# YOTSUBA_GNSS-receiver_MAX_ver_1_4_1.net
KiCad netlist of a schematic drawn in EAGLE
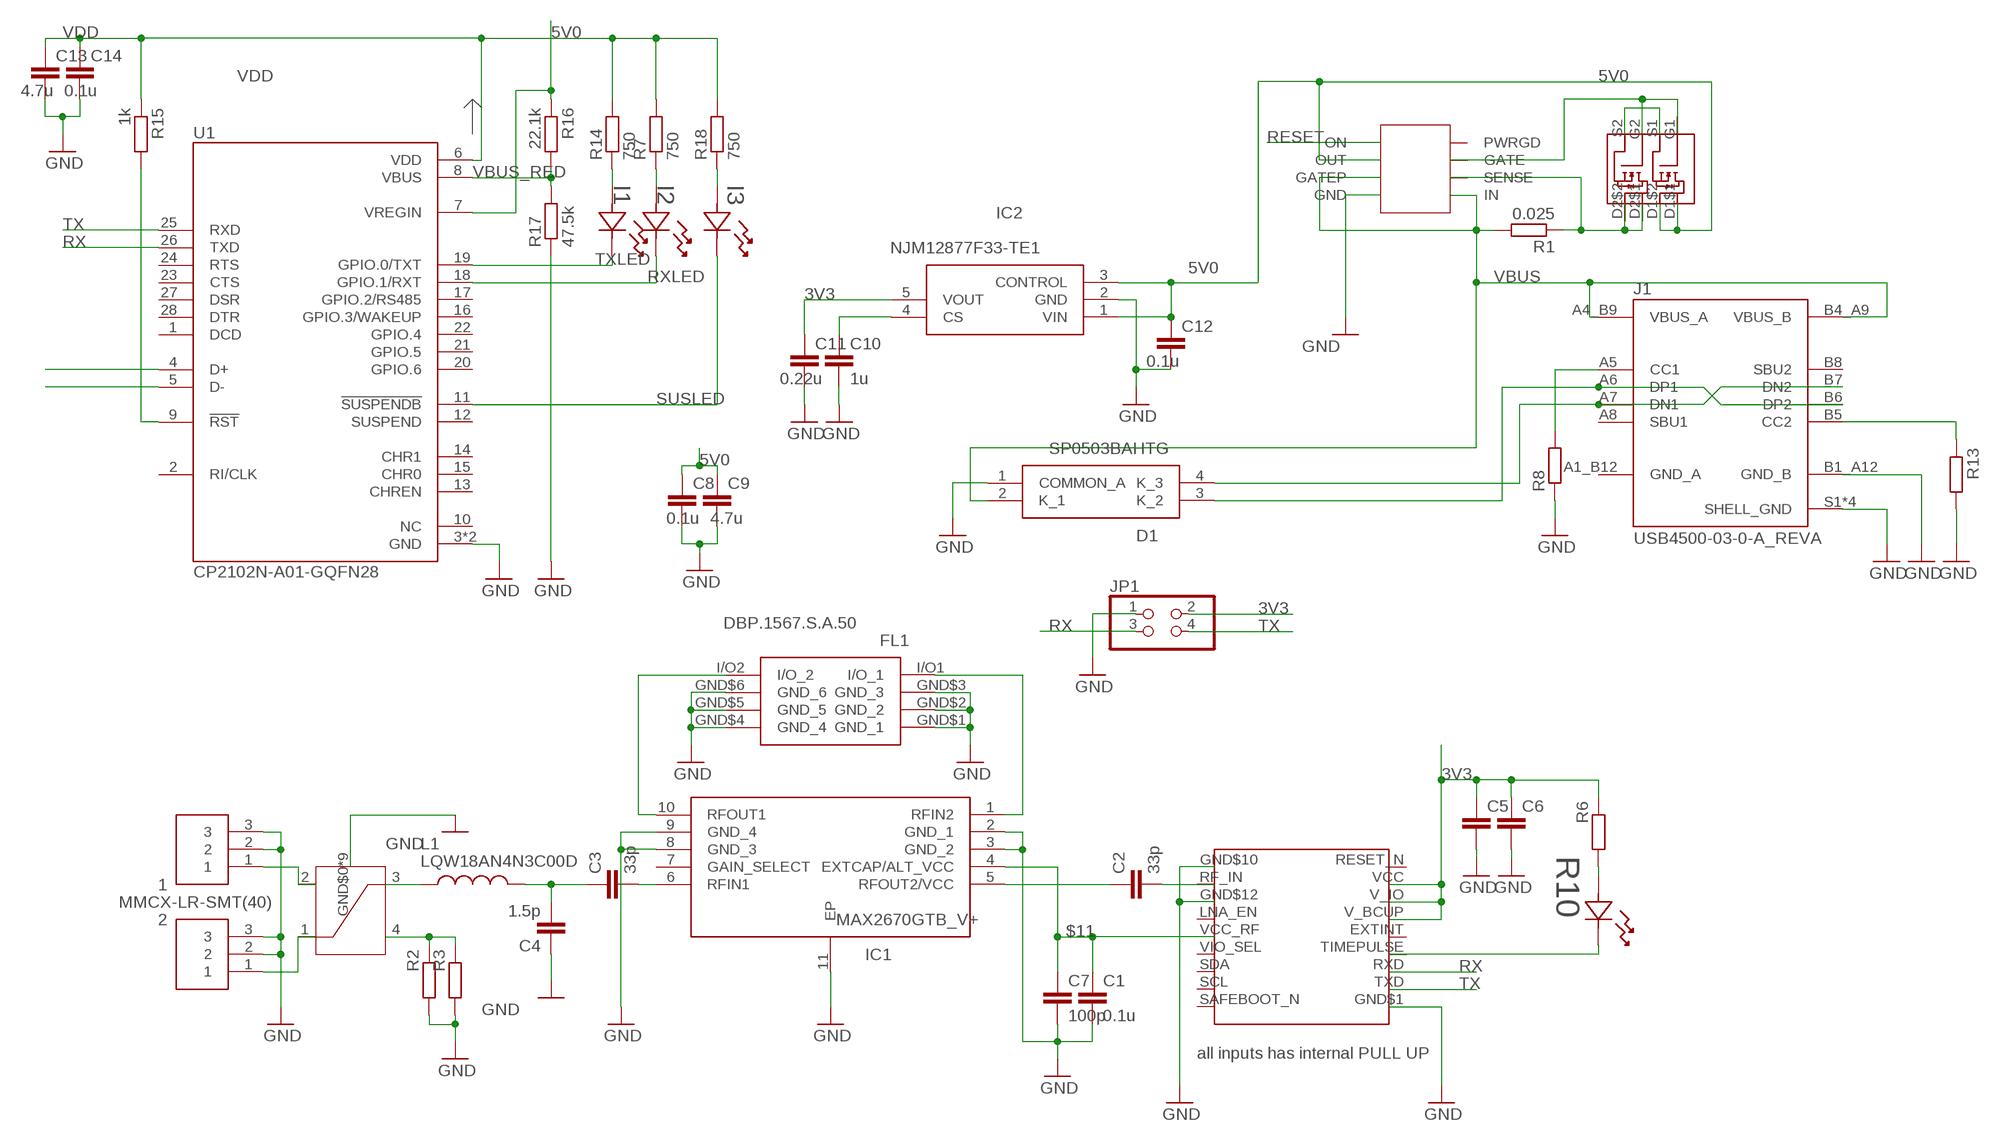
[diagram p0: schematic, sheet 1]

(export (version "E")
  (design (tool "Eeschema 10.0.6"))
  (components
    (comp (ref "1")
      (value "MMCX-LR-SMT(40)")
      (footprint "eagle-import:MMCX-LR-SMT(40)")
      (libsource (lib "eagle-import") (part "MMCX-LR-SMT(40)"))
    )
    (comp (ref "2")
      (value "MMCX-LR-SMT(40)")
      (footprint "eagle-import:MMCX-LR-SMT(40)")
      (libsource (lib "eagle-import") (part "MMCX-LR-SMT(40)"))
    )
    (comp (ref "C1")
      (value "0.1u")
      (footprint "eagle-import:C1608")
      (libsource (lib "eagle-import") (part "C-EUC1608"))
    )
    (comp (ref "C2")
      (value "33p")
      (footprint "eagle-import:C1608")
      (libsource (lib "eagle-import") (part "C-EUC1608"))
    )
    (comp (ref "C3")
      (value "33p")
      (footprint "eagle-import:C1608")
      (libsource (lib "eagle-import") (part "C-EUC1608"))
    )
    (comp (ref "C4")
      (value "1.5p")
      (footprint "eagle-import:C1608")
      (libsource (lib "eagle-import") (part "C-EUC1608"))
    )
    (comp (ref "C5")
      (value "C-EUC1608")
      (footprint "eagle-import:C1608")
      (libsource (lib "eagle-import") (part "C-EUC1608"))
    )
    (comp (ref "C6")
      (value "C-EUC1608")
      (footprint "eagle-import:C1608")
      (libsource (lib "eagle-import") (part "C-EUC1608"))
    )
    (comp (ref "C7")
      (value "100p")
      (footprint "eagle-import:C1608")
      (libsource (lib "eagle-import") (part "C-EUC1608"))
    )
    (comp (ref "C8")
      (value "0.1u")
      (footprint "eagle-import:C1608")
      (libsource (lib "eagle-import") (part "C-EUC1608"))
    )
    (comp (ref "C9")
      (value "4.7u")
      (footprint "eagle-import:C1608")
      (libsource (lib "eagle-import") (part "C-EUC1608"))
    )
    (comp (ref "C10")
      (value "1u")
      (footprint "eagle-import:C1608")
      (libsource (lib "eagle-import") (part "C-EUC1608"))
    )
    (comp (ref "C11")
      (value "0.22u")
      (footprint "eagle-import:C1608")
      (libsource (lib "eagle-import") (part "C-EUC1608"))
    )
    (comp (ref "C12")
      (value "0.1u")
      (footprint "eagle-import:C1608")
      (libsource (lib "eagle-import") (part "C-EUC1608"))
    )
    (comp (ref "C13")
      (value "4.7u")
      (footprint "eagle-import:C1608")
      (libsource (lib "eagle-import") (part "C-EUC1608"))
    )
    (comp (ref "C14")
      (value "0.1u")
      (footprint "eagle-import:C1608")
      (libsource (lib "eagle-import") (part "C-EUC1608"))
    )
    (comp (ref "D1")
      (value "SP0503BAHTG")
      (footprint "eagle-import:SP0503BAHTG")
      (fields (field (name "MOUSER_PART_NUMBER") "576-SP0503BAHTG"))
      (libsource (lib "eagle-import") (part "SP0503BAHTG"))
    )
    (comp (ref "FL1")
      (value "DBP.1567.S.A.50")
      (footprint "eagle-import:DBP1567SA50")
      (libsource (lib "eagle-import") (part "DBP.1567.S.A.50"))
    )
    (comp (ref "I1")
      (value "SML-E12P8WT86")
      (footprint "eagle-import:LED_SMLD12_ROM")
      (fields (field (name "COPYRIGHT") "Copyright (C) 2023 Ultra Librarian. All rights reserved."))
      (libsource (lib "eagle-import") (part "SML-E12P8WT86"))
    )
    (comp (ref "I2")
      (value "SML-E12P8WT86")
      (footprint "eagle-import:LED_SMLD12_ROM")
      (fields (field (name "COPYRIGHT") "Copyright (C) 2023 Ultra Librarian. All rights reserved."))
      (libsource (lib "eagle-import") (part "SML-E12P8WT86"))
    )
    (comp (ref "I3")
      (value "SML-E12P8WT86")
      (footprint "eagle-import:LED_SMLD12_ROM")
      (fields (field (name "COPYRIGHT") "Copyright (C) 2023 Ultra Librarian. All rights reserved."))
      (libsource (lib "eagle-import") (part "SML-E12P8WT86"))
    )
    (comp (ref "IC1")
      (value "MAX2670GTB_V+")
      (footprint "eagle-import:SON50P300X300X80-11N")
      (fields
        (field (name "MANUFACTURER_PART_NUMBER") "MAX2670GTB/V+")
        (field (name "MOUSER_PART_NUMBER") "700-MAX2670GTB/V+")
      )
      (libsource (lib "eagle-import") (part "MAX2670GTB_V+"))
    )
    (comp (ref "IC2")
      (value "NJM12877F33-TE1")
      (footprint "eagle-import:SOT95P280X120-5N")
      (fields (field (name "MOUSER_PART_NUMBER") "513-NJM12877F33-TE1"))
      (libsource (lib "eagle-import") (part "NJM12877F33-TE1"))
    )
    (comp (ref "J1")
      (value "USB4500-03-0-A_REVA")
      (footprint "eagle-import:GCT_USB4500-03-0-A_REVA")
      (fields
        (field (name "DIGI-KEY_PART_NUMBER") "2073-USB4500-03-0-ATR-ND")
        (field (name "MF") "Global Connector Technology")
        (field (name "MP") "USB4500-03-0-A")
      )
      (libsource (lib "eagle-import") (part "USB4500-03-0-A_REVA"))
    )
    (comp (ref "JP1")
      (value "PINHD-2X2")
      (footprint "eagle-import:2X02")
      (libsource (lib "eagle-import") (part "PINHD-2X2"))
    )
    (comp (ref "L1")
      (value "LQW18AN4N3C00D")
      (footprint "eagle-import:INDC1608X100N")
      (fields (field (name "DIGIKEY_PART_NUMBER") "490-6896-2-ND") (field (name "MF") "Murata"))
      (libsource (lib "eagle-import") (part "LQW18AN4N3C00D"))
    )
    (comp (ref "R1")
      (value "0.025")
      (footprint "eagle-import:R0603")
      (libsource (lib "eagle-import") (part "R-EU_R0603"))
    )
    (comp (ref "R2")
      (value "R-EU_R0603")
      (footprint "eagle-import:R0603")
      (libsource (lib "eagle-import") (part "R-EU_R0603"))
    )
    (comp (ref "R3")
      (value "R-EU_R0603")
      (footprint "eagle-import:R0603")
      (libsource (lib "eagle-import") (part "R-EU_R0603"))
    )
    (comp (ref "R6")
      (value "R-EU_R0603")
      (footprint "eagle-import:R0603")
      (libsource (lib "eagle-import") (part "R-EU_R0603"))
    )
    (comp (ref "R7")
      (value "750")
      (footprint "eagle-import:R0603")
      (libsource (lib "eagle-import") (part "R-EU_R0603"))
    )
    (comp (ref "R8")
      (value "R-EU_R0603")
      (footprint "eagle-import:R0603")
      (libsource (lib "eagle-import") (part "R-EU_R0603"))
    )
    (comp (ref "R10")
      (value "SML-E12P8WT86")
      (footprint "eagle-import:LED_SMLD12_ROM")
      (fields (field (name "COPYRIGHT") "Copyright (C) 2023 Ultra Librarian. All rights reserved."))
      (libsource (lib "eagle-import") (part "SML-E12P8WT86"))
    )
    (comp (ref "R13")
      (value "R-EU_R0603")
      (footprint "eagle-import:R0603")
      (libsource (lib "eagle-import") (part "R-EU_R0603"))
    )
    (comp (ref "R14")
      (value "750")
      (footprint "eagle-import:R0603")
      (libsource (lib "eagle-import") (part "R-EU_R0603"))
    )
    (comp (ref "R15")
      (value "1k")
      (footprint "eagle-import:R0603")
      (libsource (lib "eagle-import") (part "R-EU_R0603"))
    )
    (comp (ref "R16")
      (value "22.1k")
      (footprint "eagle-import:R0603")
      (libsource (lib "eagle-import") (part "R-EU_R0603"))
    )
    (comp (ref "R17")
      (value "47.5k")
      (footprint "eagle-import:R0603")
      (libsource (lib "eagle-import") (part "R-EU_R0603"))
    )
    (comp (ref "R18")
      (value "750")
      (footprint "eagle-import:R0603")
      (libsource (lib "eagle-import") (part "R-EU_R0603"))
    )
    (comp (ref "U$1")
      (value "MAX_M10S")
      (footprint "eagle-import:MAX-M10S")
      (libsource (lib "eagle-import") (part "MAX_M10S"))
    )
    (comp (ref "U$3")
      (value "HC125.A")
      (footprint "eagle-import:HC125.A")
      (libsource (lib "eagle-import") (part "HC125.A"))
    )
    (comp (ref "U$7")
      (value "DMG6898LSD")
      (footprint "eagle-import:SOIC127P600X150-8N")
      (libsource (lib "eagle-import") (part "DMG6898LSD"))
    )
    (comp (ref "U$8")
      (value "LTC4361")
      (footprint "eagle-import:SOP65P280X100-8N")
      (libsource (lib "eagle-import") (part "LTC4361"))
    )
    (comp (ref "U1")
      (value "CP2102N-A01-GQFN28")
      (footprint "eagle-import:QFN50P500X500X80-29N")
      (fields (field (name "MF") "Silicon Labs"))
      (libsource (lib "eagle-import") (part "CP2102N-A01-GQFN28"))
    )
  )
  (nets
    (net (code "1") (name "/$11") (class "Default")
      (node (ref "C1") (pin "1") (pinfunction "1_1") (pintype "passive"))
      (node (ref "C7") (pin "1") (pinfunction "1_1") (pintype "passive"))
      (node (ref "IC1") (pin "4") (pinfunction "EXTCAP/ALT_VCC_4") (pintype "bidirectional"))
      (node (ref "U$1") (pin "VCC_RF") (pinfunction "VCC_RF_VCC_RF") (pintype "bidirectional"))
    )
    (net (code "2") (name "/3V3") (class "Default")
      (node (ref "C11") (pin "1") (pinfunction "1_1") (pintype "passive"))
      (node (ref "C5") (pin "1") (pinfunction "1_1") (pintype "passive"))
      (node (ref "C6") (pin "1") (pinfunction "1_1") (pintype "passive"))
      (node (ref "IC2") (pin "5") (pinfunction "VOUT_5") (pintype "bidirectional"))
      (node (ref "JP1") (pin "2") (pinfunction "2_2") (pintype "passive"))
      (node (ref "R6") (pin "2") (pinfunction "2_2") (pintype "passive"))
      (node (ref "U$1") (pin "VCC") (pinfunction "VCC_VCC") (pintype "bidirectional"))
      (node (ref "U$1") (pin "V_BCUP") (pinfunction "V_BCKP_V_BCUP") (pintype "bidirectional"))
      (node (ref "U$1") (pin "V_IO") (pinfunction "V_IO_V_IO") (pintype "bidirectional"))
    )
    (net (code "3") (name "/5V0") (class "Default")
      (node (ref "C12") (pin "1") (pinfunction "1_1") (pintype "passive"))
      (node (ref "C8") (pin "1") (pinfunction "1_1") (pintype "passive"))
      (node (ref "C9") (pin "1") (pinfunction "1_1") (pintype "passive"))
      (node (ref "IC2") (pin "1") (pinfunction "VIN_1") (pintype "bidirectional"))
      (node (ref "IC2") (pin "3") (pinfunction "CONTROL_3") (pintype "bidirectional"))
      (node (ref "R16") (pin "1") (pinfunction "1_1") (pintype "passive"))
      (node (ref "U$7") (pin "D1$1") (pinfunction "D1$1_D1$1") (pintype "bidirectional"))
      (node (ref "U$7") (pin "D1$2") (pinfunction "D1$2_D1$2") (pintype "bidirectional"))
      (node (ref "U$8") (pin "OUT") (pinfunction "OUT_OUT") (pintype "bidirectional"))
      (node (ref "U1") (pin "7") (pinfunction "VREGIN_7") (pintype "power_in"))
    )
    (net (code "4") (name "/D+") (class "Default")
      (node (ref "D1") (pin "3") (pinfunction "K_2_3") (pintype "bidirectional"))
      (node (ref "J1") (pin "A6") (pinfunction "DP1_A6") (pintype "bidirectional"))
      (node (ref "J1") (pin "B6") (pinfunction "DP2_B6") (pintype "bidirectional"))
      (node (ref "U1") (pin "4") (pinfunction "D+_4") (pintype "bidirectional"))
    )
    (net (code "5") (name "/D-") (class "Default")
      (node (ref "D1") (pin "4") (pinfunction "K_3_4") (pintype "bidirectional"))
      (node (ref "J1") (pin "A7") (pinfunction "DN1_A7") (pintype "bidirectional"))
      (node (ref "J1") (pin "B7") (pinfunction "DN2_B7") (pintype "bidirectional"))
      (node (ref "U1") (pin "5") (pinfunction "D-_5") (pintype "bidirectional"))
    )
    (net (code "6") (name "/GND_A") (class "Default")
      (node (ref "J1") (pin "A1_B12") (pinfunction "GND_A_A1_B12") (pintype "power_in"))
    )
    (net (code "7") (name "/RESET") (class "Default")
      (node (ref "U$8") (pin "ON") (pinfunction "ON_ON") (pintype "bidirectional"))
    )
    (net (code "8") (name "/RX") (class "Default")
      (node (ref "JP1") (pin "3") (pinfunction "3_3") (pintype "passive"))
      (node (ref "U$1") (pin "RXD") (pinfunction "RXD_RXD") (pintype "bidirectional"))
      (node (ref "U1") (pin "26") (pinfunction "TXD_26") (pintype "output"))
    )
    (net (code "9") (name "/RXLED") (class "Default")
      (node (ref "I2") (pin "1") (pinfunction "1_1") (pintype "passive"))
      (node (ref "U1") (pin "18") (pinfunction "GPIO.1/RXT_18") (pintype "bidirectional"))
    )
    (net (code "10") (name "/SUSLED") (class "Default")
      (node (ref "I3") (pin "1") (pinfunction "1_1") (pintype "passive"))
      (node (ref "U1") (pin "11") (pinfunction "~{SUSPENDB}_11") (pintype "output"))
    )
    (net (code "11") (name "/TX") (class "Default")
      (node (ref "JP1") (pin "4") (pinfunction "4_4") (pintype "passive"))
      (node (ref "U$1") (pin "TXD") (pinfunction "TXD_TXD") (pintype "bidirectional"))
      (node (ref "U1") (pin "25") (pinfunction "RXD_25") (pintype "input"))
    )
    (net (code "12") (name "/TXLED") (class "Default")
      (node (ref "I1") (pin "1") (pinfunction "1_1") (pintype "passive"))
      (node (ref "U1") (pin "19") (pinfunction "GPIO.0/TXT_19") (pintype "bidirectional"))
    )
    (net (code "13") (name "/VBUS") (class "Default")
      (node (ref "D1") (pin "2") (pinfunction "K_1_2") (pintype "bidirectional"))
      (node (ref "J1") (pin "A4_B9") (pinfunction "VBUS_A_A4_B9") (pintype "power_in"))
      (node (ref "J1") (pin "B4_A9") (pinfunction "VBUS_B_B4_A9") (pintype "power_in"))
      (node (ref "R1") (pin "2") (pinfunction "2_2") (pintype "passive"))
      (node (ref "U$8") (pin "GATEP") (pinfunction "GATEP_GATEP") (pintype "bidirectional"))
      (node (ref "U$8") (pin "IN") (pinfunction "IN_IN") (pintype "bidirectional"))
    )
    (net (code "14") (name "/VBUS_RED") (class "Default")
      (node (ref "R16") (pin "2") (pinfunction "2_2") (pintype "passive"))
      (node (ref "R17") (pin "2") (pinfunction "2_2") (pintype "passive"))
      (node (ref "U1") (pin "8") (pinfunction "VBUS_8") (pintype "power_in"))
    )
    (net (code "15") (name "/VDD") (class "Default")
      (node (ref "C13") (pin "1") (pinfunction "1_1") (pintype "passive"))
      (node (ref "C14") (pin "1") (pinfunction "1_1") (pintype "passive"))
      (node (ref "R14") (pin "2") (pinfunction "2_2") (pintype "passive"))
      (node (ref "R15") (pin "1") (pinfunction "1_1") (pintype "passive"))
      (node (ref "R18") (pin "2") (pinfunction "2_2") (pintype "passive"))
      (node (ref "R7") (pin "2") (pinfunction "2_2") (pintype "passive"))
      (node (ref "U1") (pin "6") (pinfunction "VDD_6") (pintype "power_in"))
    )
    (net (code "16") (name "GND") (class "Default")
      (node (ref "1") (pin "2") (pinfunction "2_2") (pintype "bidirectional"))
      (node (ref "1") (pin "3") (pinfunction "3_3") (pintype "bidirectional"))
      (node (ref "2") (pin "2") (pinfunction "2_2") (pintype "bidirectional"))
      (node (ref "2") (pin "3") (pinfunction "3_3") (pintype "bidirectional"))
      (node (ref "C1") (pin "2") (pinfunction "2_2") (pintype "passive"))
      (node (ref "C10") (pin "2") (pinfunction "2_2") (pintype "passive"))
      (node (ref "C11") (pin "2") (pinfunction "2_2") (pintype "passive"))
      (node (ref "C12") (pin "2") (pinfunction "2_2") (pintype "passive"))
      (node (ref "C13") (pin "2") (pinfunction "2_2") (pintype "passive"))
      (node (ref "C14") (pin "2") (pinfunction "2_2") (pintype "passive"))
      (node (ref "C4") (pin "1") (pinfunction "1_1") (pintype "passive"))
      (node (ref "C5") (pin "2") (pinfunction "2_2") (pintype "passive"))
      (node (ref "C6") (pin "2") (pinfunction "2_2") (pintype "passive"))
      (node (ref "C7") (pin "2") (pinfunction "2_2") (pintype "passive"))
      (node (ref "C8") (pin "2") (pinfunction "2_2") (pintype "passive"))
      (node (ref "C9") (pin "2") (pinfunction "2_2") (pintype "passive"))
      (node (ref "D1") (pin "1") (pinfunction "COMMON_A_1") (pintype "bidirectional"))
      (node (ref "FL1") (pin "GND$1") (pinfunction "GND_1_GND$1") (pintype "bidirectional"))
      (node (ref "FL1") (pin "GND$2") (pinfunction "GND_2_GND$2") (pintype "bidirectional"))
      (node (ref "FL1") (pin "GND$3") (pinfunction "GND_3_GND$3") (pintype "bidirectional"))
      (node (ref "FL1") (pin "GND$4") (pinfunction "GND_4_GND$4") (pintype "bidirectional"))
      (node (ref "FL1") (pin "GND$5") (pinfunction "GND_5_GND$5") (pintype "bidirectional"))
      (node (ref "FL1") (pin "GND$6") (pinfunction "GND_6_GND$6") (pintype "bidirectional"))
      (node (ref "IC1") (pin "11") (pinfunction "EP_11") (pintype "bidirectional"))
      (node (ref "IC1") (pin "2") (pinfunction "GND_1_2") (pintype "bidirectional"))
      (node (ref "IC1") (pin "3") (pinfunction "GND_2_3") (pintype "bidirectional"))
      (node (ref "IC1") (pin "8") (pinfunction "GND_3_8") (pintype "bidirectional"))
      (node (ref "IC1") (pin "9") (pinfunction "GND_4_9") (pintype "bidirectional"))
      (node (ref "IC2") (pin "2") (pinfunction "GND_2") (pintype "bidirectional"))
      (node (ref "J1") (pin "B1_A12") (pinfunction "GND_B_B1_A12") (pintype "power_in"))
      (node (ref "J1") (pin "S1") (pinfunction "SHELL_GND_S1") (pintype "power_in"))
      (node (ref "J1") (pin "S2") (pinfunction "SHELL_GND_S2") (pintype "power_in"))
      (node (ref "J1") (pin "S3") (pinfunction "SHELL_GND_S3") (pintype "power_in"))
      (node (ref "J1") (pin "S4") (pinfunction "SHELL_GND_S4") (pintype "power_in"))
      (node (ref "JP1") (pin "1") (pinfunction "1_1") (pintype "passive"))
      (node (ref "R13") (pin "2") (pinfunction "2_2") (pintype "passive"))
      (node (ref "R17") (pin "1") (pinfunction "1_1") (pintype "passive"))
      (node (ref "R2") (pin "1") (pinfunction "1_1") (pintype "passive"))
      (node (ref "R3") (pin "1") (pinfunction "1_1") (pintype "passive"))
      (node (ref "R8") (pin "1") (pinfunction "1_1") (pintype "passive"))
      (node (ref "U$1") (pin "GND$1") (pinfunction "GND$1_GND$1") (pintype "bidirectional"))
      (node (ref "U$1") (pin "GND$10") (pinfunction "GND$10_GND$10") (pintype "bidirectional"))
      (node (ref "U$1") (pin "GND$12") (pinfunction "GND$12_GND$12") (pintype "bidirectional"))
      (node (ref "U$3") (pin "GND$0") (pinfunction "GND_GND$0") (pintype "bidirectional"))
      (node (ref "U$3") (pin "GND$1") (pinfunction "GND_GND$1") (pintype "bidirectional"))
      (node (ref "U$3") (pin "GND$2") (pinfunction "GND_GND$2") (pintype "bidirectional"))
      (node (ref "U$3") (pin "GND$3") (pinfunction "GND_GND$3") (pintype "bidirectional"))
      (node (ref "U$3") (pin "GND$4") (pinfunction "GND_GND$4") (pintype "bidirectional"))
      (node (ref "U$3") (pin "GND$5") (pinfunction "GND_GND$5") (pintype "bidirectional"))
      (node (ref "U$3") (pin "GND$6") (pinfunction "GND_GND$6") (pintype "bidirectional"))
      (node (ref "U$3") (pin "GND$7") (pinfunction "GND_GND$7") (pintype "bidirectional"))
      (node (ref "U$3") (pin "GND$8") (pinfunction "GND_GND$8") (pintype "bidirectional"))
      (node (ref "U$8") (pin "GND") (pinfunction "GND_GND") (pintype "bidirectional"))
      (node (ref "U1") (pin "29") (pinfunction "GND_29") (pintype "power_in"))
      (node (ref "U1") (pin "3") (pinfunction "GND_3") (pintype "power_in"))
    )
    (net (code "17") (name "Net-(1-Pad1)") (class "Default")
      (node (ref "1") (pin "1") (pinfunction "1_1") (pintype "bidirectional"))
      (node (ref "U$3") (pin "2") (pinfunction "2_2") (pintype "bidirectional"))
    )
    (net (code "18") (name "Net-(2-Pad1)") (class "Default")
      (node (ref "2") (pin "1") (pinfunction "1_1") (pintype "bidirectional"))
      (node (ref "U$3") (pin "1") (pinfunction "1_1") (pintype "bidirectional"))
    )
    (net (code "19") (name "Net-(C2-Pad2)") (class "Default")
      (node (ref "C2") (pin "2") (pinfunction "2_2") (pintype "passive"))
      (node (ref "U$1") (pin "RF_IN") (pinfunction "RF_IN_RF_IN") (pintype "bidirectional"))
    )
    (net (code "20") (name "Net-(C3-Pad1)") (class "Default")
      (node (ref "C3") (pin "1") (pinfunction "1_1") (pintype "passive"))
      (node (ref "C4") (pin "2") (pinfunction "2_2") (pintype "passive"))
      (node (ref "L1") (pin "2") (pinfunction "2_2") (pintype "passive"))
    )
    (net (code "21") (name "Net-(FL1-I{slash}O_1)") (class "Default")
      (node (ref "FL1") (pin "I/O1") (pinfunction "I/O_1_I/O1") (pintype "bidirectional"))
      (node (ref "IC1") (pin "1") (pinfunction "RFIN2_1") (pintype "bidirectional"))
    )
    (net (code "22") (name "Net-(FL1-I{slash}O_2)") (class "Default")
      (node (ref "FL1") (pin "I/O2") (pinfunction "I/O_2_I/O2") (pintype "bidirectional"))
      (node (ref "IC1") (pin "10") (pinfunction "RFOUT1_10") (pintype "bidirectional"))
    )
    (net (code "23") (name "Net-(I1-Pad2)") (class "Default")
      (node (ref "I1") (pin "2") (pinfunction "2_2") (pintype "passive"))
      (node (ref "R14") (pin "1") (pinfunction "1_1") (pintype "passive"))
    )
    (net (code "24") (name "Net-(I2-Pad2)") (class "Default")
      (node (ref "I2") (pin "2") (pinfunction "2_2") (pintype "passive"))
      (node (ref "R7") (pin "1") (pinfunction "1_1") (pintype "passive"))
    )
    (net (code "25") (name "Net-(I3-Pad2)") (class "Default")
      (node (ref "I3") (pin "2") (pinfunction "2_2") (pintype "passive"))
      (node (ref "R18") (pin "1") (pinfunction "1_1") (pintype "passive"))
    )
    (net (code "26") (name "Net-(IC1-RFIN1)") (class "Default")
      (node (ref "C3") (pin "2") (pinfunction "2_2") (pintype "passive"))
      (node (ref "IC1") (pin "6") (pinfunction "RFIN1_6") (pintype "bidirectional"))
    )
    (net (code "27") (name "Net-(IC1-RFOUT2{slash}VCC)") (class "Default")
      (node (ref "C2") (pin "1") (pinfunction "1_1") (pintype "passive"))
      (node (ref "IC1") (pin "5") (pinfunction "RFOUT2/VCC_5") (pintype "bidirectional"))
    )
    (net (code "28") (name "Net-(IC2-CS)") (class "Default")
      (node (ref "C10") (pin "1") (pinfunction "1_1") (pintype "passive"))
      (node (ref "IC2") (pin "4") (pinfunction "CS_4") (pintype "bidirectional"))
    )
    (net (code "29") (name "Net-(J1-CC1)") (class "Default")
      (node (ref "J1") (pin "A5") (pinfunction "CC1_A5") (pintype "bidirectional"))
      (node (ref "R8") (pin "2") (pinfunction "2_2") (pintype "passive"))
    )
    (net (code "30") (name "Net-(J1-CC2)") (class "Default")
      (node (ref "J1") (pin "B5") (pinfunction "CC2_B5") (pintype "bidirectional"))
      (node (ref "R13") (pin "1") (pinfunction "1_1") (pintype "passive"))
    )
    (net (code "31") (name "Net-(L1-Pad1)") (class "Default")
      (node (ref "L1") (pin "1") (pinfunction "1_1") (pintype "passive"))
      (node (ref "U$3") (pin "3") (pinfunction "3_3") (pintype "bidirectional"))
    )
    (net (code "32") (name "Net-(R1-Pad1)") (class "Default")
      (node (ref "R1") (pin "1") (pinfunction "1_1") (pintype "passive"))
      (node (ref "U$7") (pin "D2$1") (pinfunction "D2$1_D2$1") (pintype "bidirectional"))
      (node (ref "U$7") (pin "D2$2") (pinfunction "D2$2_D2$2") (pintype "bidirectional"))
      (node (ref "U$8") (pin "SENSE") (pinfunction "SENSE_SENSE") (pintype "bidirectional"))
    )
    (net (code "33") (name "Net-(R2-Pad2)") (class "Default")
      (node (ref "R2") (pin "2") (pinfunction "2_2") (pintype "passive"))
      (node (ref "R3") (pin "2") (pinfunction "2_2") (pintype "passive"))
      (node (ref "U$3") (pin "4") (pinfunction "4_4") (pintype "bidirectional"))
    )
    (net (code "34") (name "Net-(R10-Pad1)") (class "Default")
      (node (ref "R10") (pin "1") (pinfunction "1_1") (pintype "passive"))
      (node (ref "U$1") (pin "TIMEPULSE") (pinfunction "TIMEPULSE_TIMEPULSE") (pintype "bidirectional"))
    )
    (net (code "35") (name "Net-(R10-Pad2)") (class "Default")
      (node (ref "R10") (pin "2") (pinfunction "2_2") (pintype "passive"))
      (node (ref "R6") (pin "1") (pinfunction "1_1") (pintype "passive"))
    )
    (net (code "36") (name "Net-(U$7-PadG1)") (class "Default")
      (node (ref "U$7") (pin "G1") (pinfunction "G1_G1") (pintype "bidirectional"))
      (node (ref "U$7") (pin "G2") (pinfunction "G2_G2") (pintype "bidirectional"))
      (node (ref "U$8") (pin "GATE") (pinfunction "GATE_GATE") (pintype "bidirectional"))
    )
    (net (code "37") (name "Net-(U$7-PadS1)") (class "Default")
      (node (ref "U$7") (pin "S1") (pinfunction "S1_S1") (pintype "bidirectional"))
      (node (ref "U$7") (pin "S2") (pinfunction "S2_S2") (pintype "bidirectional"))
    )
    (net (code "38") (name "Net-(U1-~{RST})") (class "Default")
      (node (ref "R15") (pin "2") (pinfunction "2_2") (pintype "passive"))
      (node (ref "U1") (pin "9") (pinfunction "~{RST}_9") (pintype "input"))
    )
    (net (code "39") (name "unconnected-(IC1-GAIN_SELECT-Pad7)") (class "Default")
      (node (ref "IC1") (pin "7") (pinfunction "GAIN_SELECT_7") (pintype "bidirectional"))
    )
    (net (code "40") (name "unconnected-(J1-SBU1-PadA8)") (class "Default")
      (node (ref "J1") (pin "A8") (pinfunction "SBU1_A8") (pintype "bidirectional"))
    )
    (net (code "41") (name "unconnected-(J1-SBU2-PadB8)") (class "Default")
      (node (ref "J1") (pin "B8") (pinfunction "SBU2_B8") (pintype "bidirectional"))
    )
    (net (code "42") (name "unconnected-(U$1-PadEXTINT)") (class "Default")
      (node (ref "U$1") (pin "EXTINT") (pinfunction "EXTINT_EXTINT") (pintype "bidirectional"))
    )
    (net (code "43") (name "unconnected-(U$1-PadLNA_EN)") (class "Default")
      (node (ref "U$1") (pin "LNA_EN") (pinfunction "LNA_EN_LNA_EN") (pintype "bidirectional"))
    )
    (net (code "44") (name "unconnected-(U$1-PadRESET_N)") (class "Default")
      (node (ref "U$1") (pin "RESET_N") (pinfunction "RESET_N_RESET_N") (pintype "bidirectional"))
    )
    (net (code "45") (name "unconnected-(U$1-PadSAFEBOOT_N)") (class "Default")
      (node (ref "U$1") (pin "SAFEBOOT_N") (pinfunction "SAFEBOOT_N_SAFEBOOT_N") (pintype "bidirectional"))
    )
    (net (code "46") (name "unconnected-(U$1-PadSCL)") (class "Default")
      (node (ref "U$1") (pin "SCL") (pinfunction "SCL_SCL") (pintype "bidirectional"))
    )
    (net (code "47") (name "unconnected-(U$1-PadSDA)") (class "Default")
      (node (ref "U$1") (pin "SDA") (pinfunction "SDA_SDA") (pintype "bidirectional"))
    )
    (net (code "48") (name "unconnected-(U$1-PadVIO_SEL)") (class "Default")
      (node (ref "U$1") (pin "VIO_SEL") (pinfunction "VIO_SEL_VIO_SEL") (pintype "bidirectional"))
    )
    (net (code "49") (name "unconnected-(U$8-PadPWRGD)") (class "Default")
      (node (ref "U$8") (pin "PWRGD") (pinfunction "PWRGD_PWRGD") (pintype "bidirectional"))
    )
    (net (code "50") (name "unconnected-(U1-CHR0-Pad15)") (class "Default")
      (node (ref "U1") (pin "15") (pinfunction "CHR0_15") (pintype "output"))
    )
    (net (code "51") (name "unconnected-(U1-CHR1-Pad14)") (class "Default")
      (node (ref "U1") (pin "14") (pinfunction "CHR1_14") (pintype "output"))
    )
    (net (code "52") (name "unconnected-(U1-CHREN-Pad13)") (class "Default")
      (node (ref "U1") (pin "13") (pinfunction "CHREN_13") (pintype "output"))
    )
    (net (code "53") (name "unconnected-(U1-CTS-Pad23)") (class "Default")
      (node (ref "U1") (pin "23") (pinfunction "CTS_23") (pintype "input"))
    )
    (net (code "54") (name "unconnected-(U1-DCD-Pad1)") (class "Default")
      (node (ref "U1") (pin "1") (pinfunction "DCD_1") (pintype "input"))
    )
    (net (code "55") (name "unconnected-(U1-DSR-Pad27)") (class "Default")
      (node (ref "U1") (pin "27") (pinfunction "DSR_27") (pintype "input"))
    )
    (net (code "56") (name "unconnected-(U1-DTR-Pad28)") (class "Default")
      (node (ref "U1") (pin "28") (pinfunction "DTR_28") (pintype "output"))
    )
    (net (code "57") (name "unconnected-(U1-GPIO.2{slash}RS485-Pad17)") (class "Default")
      (node (ref "U1") (pin "17") (pinfunction "GPIO.2/RS485_17") (pintype "bidirectional"))
    )
    (net (code "58") (name "unconnected-(U1-GPIO.3{slash}WAKEUP-Pad16)") (class "Default")
      (node (ref "U1") (pin "16") (pinfunction "GPIO.3/WAKEUP_16") (pintype "bidirectional"))
    )
    (net (code "59") (name "unconnected-(U1-GPIO.4-Pad22)") (class "Default")
      (node (ref "U1") (pin "22") (pinfunction "GPIO.4_22") (pintype "bidirectional"))
    )
    (net (code "60") (name "unconnected-(U1-GPIO.5-Pad21)") (class "Default")
      (node (ref "U1") (pin "21") (pinfunction "GPIO.5_21") (pintype "bidirectional"))
    )
    (net (code "61") (name "unconnected-(U1-GPIO.6-Pad20)") (class "Default")
      (node (ref "U1") (pin "20") (pinfunction "GPIO.6_20") (pintype "bidirectional"))
    )
    (net (code "62") (name "unconnected-(U1-NC-Pad10)") (class "Default")
      (node (ref "U1") (pin "10") (pinfunction "NC_10") (pintype "no_connect"))
    )
    (net (code "63") (name "unconnected-(U1-RI{slash}CLK-Pad2)") (class "Default")
      (node (ref "U1") (pin "2") (pinfunction "RI/CLK_2") (pintype "bidirectional"))
    )
    (net (code "64") (name "unconnected-(U1-RTS-Pad24)") (class "Default")
      (node (ref "U1") (pin "24") (pinfunction "RTS_24") (pintype "output"))
    )
    (net (code "65") (name "unconnected-(U1-SUSPEND-Pad12)") (class "Default")
      (node (ref "U1") (pin "12") (pinfunction "SUSPEND_12") (pintype "output"))
    )
  )
)
